# Zotino_HD68_Adapter.net
KiCad netlist of a schematic drawn in Altium Designer
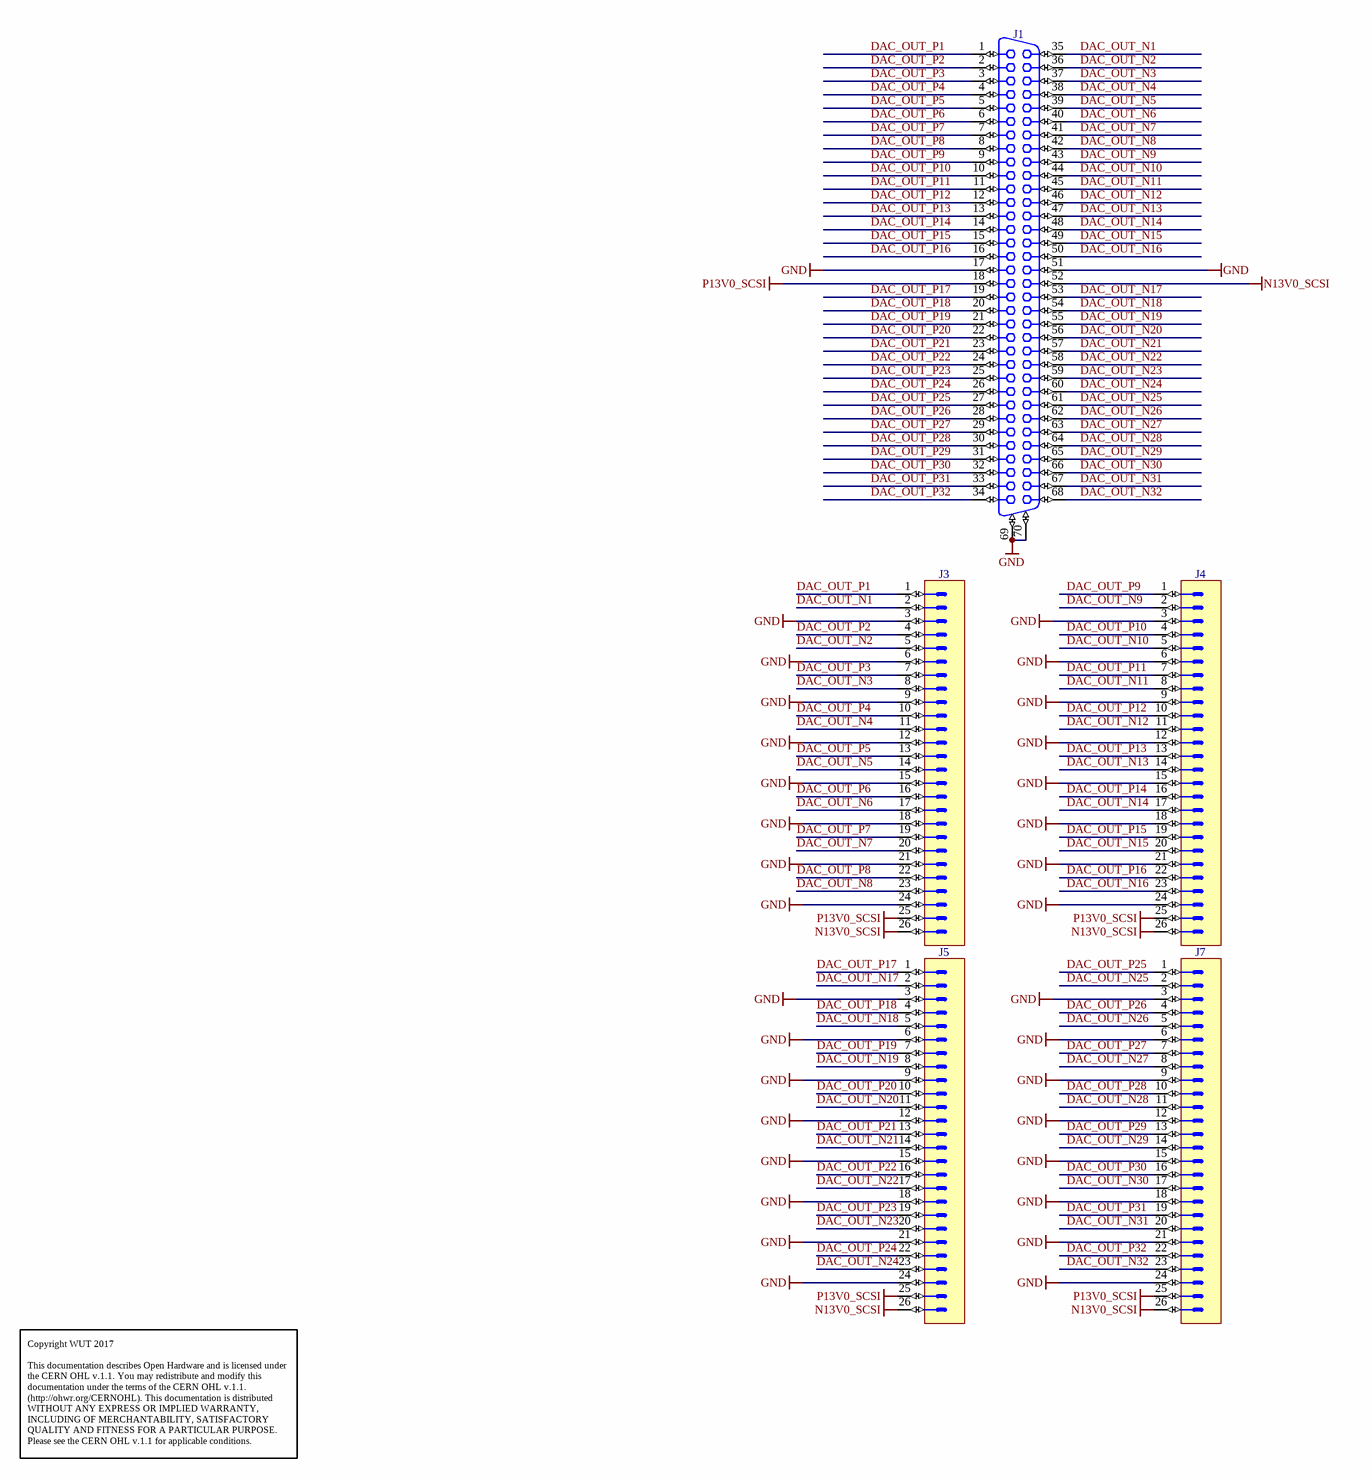
[diagram p0: Zotino_HD68_Adapter.SchDoc]

(export (version "E")
  (design (tool "Eeschema 10.0.6"))
  (components
    (comp (ref "J1")
      (value "D-SUB")
      (footprint "TYCO_5787082-7")
      (description "68 contacts, AMPLIMITE .050\", Right Angled Receptacle Series III")
      (fields
        (field (name "PART NUMBER") "TYCO_5787082-7")
        (field (name "MANUFACTURER") "TYCO ELECTRONICS")
        (field (name "AUTHOR") "CERN DEM JLC")
      )
      (libsource (lib "Connectors") (part "TYCO_5787082-7"))
    )
    (comp (ref "J3")
      (value "Header 26")
      (footprint "3M_N2526-6002RB")
      (description "Connector 26 Male")
      (fields
        (field (name "PART NUMBER") "3M_N2526-6002RB")
        (field (name "MANUFACTURER") "3M")
        (field (name "AUTHOR") "CERN DEM JLC")
      )
      (libsource (lib "Connectors") (part "Connector 26 Male"))
    )
    (comp (ref "J4")
      (value "Header 26")
      (footprint "3M_N2526-6002RB")
      (description "Connector 26 Male")
      (fields
        (field (name "PART NUMBER") "3M_N2526-6002RB")
        (field (name "MANUFACTURER") "3M")
        (field (name "AUTHOR") "CERN DEM JLC")
      )
      (libsource (lib "Connectors") (part "Connector 26 Male"))
    )
    (comp (ref "J5")
      (value "Header 26")
      (footprint "3M_N2526-6002RB")
      (description "Connector 26 Male")
      (fields
        (field (name "PART NUMBER") "3M_N2526-6002RB")
        (field (name "MANUFACTURER") "3M")
        (field (name "AUTHOR") "CERN DEM JLC")
      )
      (libsource (lib "Connectors") (part "Connector 26 Male"))
    )
    (comp (ref "J7")
      (value "Header 26")
      (footprint "3M_N2526-6002RB")
      (description "Connector 26 Male")
      (fields
        (field (name "PART NUMBER") "3M_N2526-6002RB")
        (field (name "MANUFACTURER") "3M")
        (field (name "AUTHOR") "CERN DEM JLC")
      )
      (libsource (lib "Connectors") (part "Connector 26 Male"))
    )
  )
  (nets
    (net (code "1") (name "/DAC_OUT_N1") (class "Default")
      (node (ref "J1") (pin "35") (pinfunction "35_35") (pintype "bidirectional"))
      (node (ref "J3") (pin "2") (pinfunction "2_2") (pintype "bidirectional"))
    )
    (net (code "2") (name "/DAC_OUT_N2") (class "Default")
      (node (ref "J1") (pin "36") (pinfunction "36_36") (pintype "bidirectional"))
      (node (ref "J3") (pin "5") (pinfunction "5_5") (pintype "bidirectional"))
    )
    (net (code "3") (name "/DAC_OUT_N3") (class "Default")
      (node (ref "J1") (pin "37") (pinfunction "37_37") (pintype "bidirectional"))
      (node (ref "J3") (pin "8") (pinfunction "8_8") (pintype "bidirectional"))
    )
    (net (code "4") (name "/DAC_OUT_N4") (class "Default")
      (node (ref "J1") (pin "38") (pinfunction "38_38") (pintype "bidirectional"))
      (node (ref "J3") (pin "11") (pinfunction "11_11") (pintype "bidirectional"))
    )
    (net (code "5") (name "/DAC_OUT_N5") (class "Default")
      (node (ref "J1") (pin "39") (pinfunction "39_39") (pintype "bidirectional"))
      (node (ref "J3") (pin "14") (pinfunction "14_14") (pintype "bidirectional"))
    )
    (net (code "6") (name "/DAC_OUT_N6") (class "Default")
      (node (ref "J1") (pin "40") (pinfunction "40_40") (pintype "bidirectional"))
      (node (ref "J3") (pin "17") (pinfunction "17_17") (pintype "bidirectional"))
    )
    (net (code "7") (name "/DAC_OUT_N7") (class "Default")
      (node (ref "J1") (pin "41") (pinfunction "41_41") (pintype "bidirectional"))
      (node (ref "J3") (pin "20") (pinfunction "20_20") (pintype "bidirectional"))
    )
    (net (code "8") (name "/DAC_OUT_N8") (class "Default")
      (node (ref "J1") (pin "42") (pinfunction "42_42") (pintype "bidirectional"))
      (node (ref "J3") (pin "23") (pinfunction "23_23") (pintype "bidirectional"))
    )
    (net (code "9") (name "/DAC_OUT_N9") (class "Default")
      (node (ref "J1") (pin "43") (pinfunction "43_43") (pintype "bidirectional"))
      (node (ref "J4") (pin "2") (pinfunction "2_2") (pintype "bidirectional"))
    )
    (net (code "10") (name "/DAC_OUT_N10") (class "Default")
      (node (ref "J1") (pin "44") (pinfunction "44_44") (pintype "bidirectional"))
      (node (ref "J4") (pin "5") (pinfunction "5_5") (pintype "bidirectional"))
    )
    (net (code "11") (name "/DAC_OUT_N11") (class "Default")
      (node (ref "J1") (pin "45") (pinfunction "45_45") (pintype "bidirectional"))
      (node (ref "J4") (pin "8") (pinfunction "8_8") (pintype "bidirectional"))
    )
    (net (code "12") (name "/DAC_OUT_N12") (class "Default")
      (node (ref "J1") (pin "46") (pinfunction "46_46") (pintype "bidirectional"))
      (node (ref "J4") (pin "11") (pinfunction "11_11") (pintype "bidirectional"))
    )
    (net (code "13") (name "/DAC_OUT_N13") (class "Default")
      (node (ref "J1") (pin "47") (pinfunction "47_47") (pintype "bidirectional"))
      (node (ref "J4") (pin "14") (pinfunction "14_14") (pintype "bidirectional"))
    )
    (net (code "14") (name "/DAC_OUT_N14") (class "Default")
      (node (ref "J1") (pin "48") (pinfunction "48_48") (pintype "bidirectional"))
      (node (ref "J4") (pin "17") (pinfunction "17_17") (pintype "bidirectional"))
    )
    (net (code "15") (name "/DAC_OUT_N15") (class "Default")
      (node (ref "J1") (pin "49") (pinfunction "49_49") (pintype "bidirectional"))
      (node (ref "J4") (pin "20") (pinfunction "20_20") (pintype "bidirectional"))
    )
    (net (code "16") (name "/DAC_OUT_N16") (class "Default")
      (node (ref "J1") (pin "50") (pinfunction "50_50") (pintype "bidirectional"))
      (node (ref "J4") (pin "23") (pinfunction "23_23") (pintype "bidirectional"))
    )
    (net (code "17") (name "/DAC_OUT_N17") (class "Default")
      (node (ref "J1") (pin "53") (pinfunction "53_53") (pintype "bidirectional"))
      (node (ref "J5") (pin "2") (pinfunction "2_2") (pintype "bidirectional"))
    )
    (net (code "18") (name "/DAC_OUT_N18") (class "Default")
      (node (ref "J1") (pin "54") (pinfunction "54_54") (pintype "bidirectional"))
      (node (ref "J5") (pin "5") (pinfunction "5_5") (pintype "bidirectional"))
    )
    (net (code "19") (name "/DAC_OUT_N19") (class "Default")
      (node (ref "J1") (pin "55") (pinfunction "55_55") (pintype "bidirectional"))
      (node (ref "J5") (pin "8") (pinfunction "8_8") (pintype "bidirectional"))
    )
    (net (code "20") (name "/DAC_OUT_N20") (class "Default")
      (node (ref "J1") (pin "56") (pinfunction "56_56") (pintype "bidirectional"))
      (node (ref "J5") (pin "11") (pinfunction "11_11") (pintype "bidirectional"))
    )
    (net (code "21") (name "/DAC_OUT_N21") (class "Default")
      (node (ref "J1") (pin "57") (pinfunction "57_57") (pintype "bidirectional"))
      (node (ref "J5") (pin "14") (pinfunction "14_14") (pintype "bidirectional"))
    )
    (net (code "22") (name "/DAC_OUT_N22") (class "Default")
      (node (ref "J1") (pin "58") (pinfunction "58_58") (pintype "bidirectional"))
      (node (ref "J5") (pin "17") (pinfunction "17_17") (pintype "bidirectional"))
    )
    (net (code "23") (name "/DAC_OUT_N23") (class "Default")
      (node (ref "J1") (pin "59") (pinfunction "59_59") (pintype "bidirectional"))
      (node (ref "J5") (pin "20") (pinfunction "20_20") (pintype "bidirectional"))
    )
    (net (code "24") (name "/DAC_OUT_N24") (class "Default")
      (node (ref "J1") (pin "60") (pinfunction "60_60") (pintype "bidirectional"))
      (node (ref "J5") (pin "23") (pinfunction "23_23") (pintype "bidirectional"))
    )
    (net (code "25") (name "/DAC_OUT_N25") (class "Default")
      (node (ref "J1") (pin "61") (pinfunction "61_61") (pintype "bidirectional"))
      (node (ref "J7") (pin "2") (pinfunction "2_2") (pintype "bidirectional"))
    )
    (net (code "26") (name "/DAC_OUT_N26") (class "Default")
      (node (ref "J1") (pin "62") (pinfunction "62_62") (pintype "bidirectional"))
      (node (ref "J7") (pin "5") (pinfunction "5_5") (pintype "bidirectional"))
    )
    (net (code "27") (name "/DAC_OUT_N27") (class "Default")
      (node (ref "J1") (pin "63") (pinfunction "63_63") (pintype "bidirectional"))
      (node (ref "J7") (pin "8") (pinfunction "8_8") (pintype "bidirectional"))
    )
    (net (code "28") (name "/DAC_OUT_N28") (class "Default")
      (node (ref "J1") (pin "64") (pinfunction "64_64") (pintype "bidirectional"))
      (node (ref "J7") (pin "11") (pinfunction "11_11") (pintype "bidirectional"))
    )
    (net (code "29") (name "/DAC_OUT_N29") (class "Default")
      (node (ref "J1") (pin "65") (pinfunction "65_65") (pintype "bidirectional"))
      (node (ref "J7") (pin "14") (pinfunction "14_14") (pintype "bidirectional"))
    )
    (net (code "30") (name "/DAC_OUT_N30") (class "Default")
      (node (ref "J1") (pin "66") (pinfunction "66_66") (pintype "bidirectional"))
      (node (ref "J7") (pin "17") (pinfunction "17_17") (pintype "bidirectional"))
    )
    (net (code "31") (name "/DAC_OUT_N31") (class "Default")
      (node (ref "J1") (pin "67") (pinfunction "67_67") (pintype "bidirectional"))
      (node (ref "J7") (pin "20") (pinfunction "20_20") (pintype "bidirectional"))
    )
    (net (code "32") (name "/DAC_OUT_N32") (class "Default")
      (node (ref "J1") (pin "68") (pinfunction "68_68") (pintype "bidirectional"))
      (node (ref "J7") (pin "23") (pinfunction "23_23") (pintype "bidirectional"))
    )
    (net (code "33") (name "/DAC_OUT_P1") (class "Default")
      (node (ref "J1") (pin "1") (pinfunction "1_1") (pintype "bidirectional"))
      (node (ref "J3") (pin "1") (pinfunction "1_1") (pintype "bidirectional"))
    )
    (net (code "34") (name "/DAC_OUT_P2") (class "Default")
      (node (ref "J1") (pin "2") (pinfunction "2_2") (pintype "bidirectional"))
      (node (ref "J3") (pin "4") (pinfunction "4_4") (pintype "bidirectional"))
    )
    (net (code "35") (name "/DAC_OUT_P3") (class "Default")
      (node (ref "J1") (pin "3") (pinfunction "3_3") (pintype "bidirectional"))
      (node (ref "J3") (pin "7") (pinfunction "7_7") (pintype "bidirectional"))
    )
    (net (code "36") (name "/DAC_OUT_P4") (class "Default")
      (node (ref "J1") (pin "4") (pinfunction "4_4") (pintype "bidirectional"))
      (node (ref "J3") (pin "10") (pinfunction "10_10") (pintype "bidirectional"))
    )
    (net (code "37") (name "/DAC_OUT_P5") (class "Default")
      (node (ref "J1") (pin "5") (pinfunction "5_5") (pintype "bidirectional"))
      (node (ref "J3") (pin "13") (pinfunction "13_13") (pintype "bidirectional"))
    )
    (net (code "38") (name "/DAC_OUT_P6") (class "Default")
      (node (ref "J1") (pin "6") (pinfunction "6_6") (pintype "bidirectional"))
      (node (ref "J3") (pin "16") (pinfunction "16_16") (pintype "bidirectional"))
    )
    (net (code "39") (name "/DAC_OUT_P7") (class "Default")
      (node (ref "J1") (pin "7") (pinfunction "7_7") (pintype "bidirectional"))
      (node (ref "J3") (pin "19") (pinfunction "19_19") (pintype "bidirectional"))
    )
    (net (code "40") (name "/DAC_OUT_P8") (class "Default")
      (node (ref "J1") (pin "8") (pinfunction "8_8") (pintype "bidirectional"))
      (node (ref "J3") (pin "22") (pinfunction "22_22") (pintype "bidirectional"))
    )
    (net (code "41") (name "/DAC_OUT_P9") (class "Default")
      (node (ref "J1") (pin "9") (pinfunction "9_9") (pintype "bidirectional"))
      (node (ref "J4") (pin "1") (pinfunction "1_1") (pintype "bidirectional"))
    )
    (net (code "42") (name "/DAC_OUT_P10") (class "Default")
      (node (ref "J1") (pin "10") (pinfunction "10_10") (pintype "bidirectional"))
      (node (ref "J4") (pin "4") (pinfunction "4_4") (pintype "bidirectional"))
    )
    (net (code "43") (name "/DAC_OUT_P11") (class "Default")
      (node (ref "J1") (pin "11") (pinfunction "11_11") (pintype "bidirectional"))
      (node (ref "J4") (pin "7") (pinfunction "7_7") (pintype "bidirectional"))
    )
    (net (code "44") (name "/DAC_OUT_P12") (class "Default")
      (node (ref "J1") (pin "12") (pinfunction "12_12") (pintype "bidirectional"))
      (node (ref "J4") (pin "10") (pinfunction "10_10") (pintype "bidirectional"))
    )
    (net (code "45") (name "/DAC_OUT_P13") (class "Default")
      (node (ref "J1") (pin "13") (pinfunction "13_13") (pintype "bidirectional"))
      (node (ref "J4") (pin "13") (pinfunction "13_13") (pintype "bidirectional"))
    )
    (net (code "46") (name "/DAC_OUT_P14") (class "Default")
      (node (ref "J1") (pin "14") (pinfunction "14_14") (pintype "bidirectional"))
      (node (ref "J4") (pin "16") (pinfunction "16_16") (pintype "bidirectional"))
    )
    (net (code "47") (name "/DAC_OUT_P15") (class "Default")
      (node (ref "J1") (pin "15") (pinfunction "15_15") (pintype "bidirectional"))
      (node (ref "J4") (pin "19") (pinfunction "19_19") (pintype "bidirectional"))
    )
    (net (code "48") (name "/DAC_OUT_P16") (class "Default")
      (node (ref "J1") (pin "16") (pinfunction "16_16") (pintype "bidirectional"))
      (node (ref "J4") (pin "22") (pinfunction "22_22") (pintype "bidirectional"))
    )
    (net (code "49") (name "/DAC_OUT_P17") (class "Default")
      (node (ref "J1") (pin "19") (pinfunction "19_19") (pintype "bidirectional"))
      (node (ref "J5") (pin "1") (pinfunction "1_1") (pintype "bidirectional"))
    )
    (net (code "50") (name "/DAC_OUT_P18") (class "Default")
      (node (ref "J1") (pin "20") (pinfunction "20_20") (pintype "bidirectional"))
      (node (ref "J5") (pin "4") (pinfunction "4_4") (pintype "bidirectional"))
    )
    (net (code "51") (name "/DAC_OUT_P19") (class "Default")
      (node (ref "J1") (pin "21") (pinfunction "21_21") (pintype "bidirectional"))
      (node (ref "J5") (pin "7") (pinfunction "7_7") (pintype "bidirectional"))
    )
    (net (code "52") (name "/DAC_OUT_P20") (class "Default")
      (node (ref "J1") (pin "22") (pinfunction "22_22") (pintype "bidirectional"))
      (node (ref "J5") (pin "10") (pinfunction "10_10") (pintype "bidirectional"))
    )
    (net (code "53") (name "/DAC_OUT_P21") (class "Default")
      (node (ref "J1") (pin "23") (pinfunction "23_23") (pintype "bidirectional"))
      (node (ref "J5") (pin "13") (pinfunction "13_13") (pintype "bidirectional"))
    )
    (net (code "54") (name "/DAC_OUT_P22") (class "Default")
      (node (ref "J1") (pin "24") (pinfunction "24_24") (pintype "bidirectional"))
      (node (ref "J5") (pin "16") (pinfunction "16_16") (pintype "bidirectional"))
    )
    (net (code "55") (name "/DAC_OUT_P23") (class "Default")
      (node (ref "J1") (pin "25") (pinfunction "25_25") (pintype "bidirectional"))
      (node (ref "J5") (pin "19") (pinfunction "19_19") (pintype "bidirectional"))
    )
    (net (code "56") (name "/DAC_OUT_P24") (class "Default")
      (node (ref "J1") (pin "26") (pinfunction "26_26") (pintype "bidirectional"))
      (node (ref "J5") (pin "22") (pinfunction "22_22") (pintype "bidirectional"))
    )
    (net (code "57") (name "/DAC_OUT_P25") (class "Default")
      (node (ref "J1") (pin "27") (pinfunction "27_27") (pintype "bidirectional"))
      (node (ref "J7") (pin "1") (pinfunction "1_1") (pintype "bidirectional"))
    )
    (net (code "58") (name "/DAC_OUT_P26") (class "Default")
      (node (ref "J1") (pin "28") (pinfunction "28_28") (pintype "bidirectional"))
      (node (ref "J7") (pin "4") (pinfunction "4_4") (pintype "bidirectional"))
    )
    (net (code "59") (name "/DAC_OUT_P27") (class "Default")
      (node (ref "J1") (pin "29") (pinfunction "29_29") (pintype "bidirectional"))
      (node (ref "J7") (pin "7") (pinfunction "7_7") (pintype "bidirectional"))
    )
    (net (code "60") (name "/DAC_OUT_P28") (class "Default")
      (node (ref "J1") (pin "30") (pinfunction "30_30") (pintype "bidirectional"))
      (node (ref "J7") (pin "10") (pinfunction "10_10") (pintype "bidirectional"))
    )
    (net (code "61") (name "/DAC_OUT_P29") (class "Default")
      (node (ref "J1") (pin "31") (pinfunction "31_31") (pintype "bidirectional"))
      (node (ref "J7") (pin "13") (pinfunction "13_13") (pintype "bidirectional"))
    )
    (net (code "62") (name "/DAC_OUT_P30") (class "Default")
      (node (ref "J1") (pin "32") (pinfunction "32_32") (pintype "bidirectional"))
      (node (ref "J7") (pin "16") (pinfunction "16_16") (pintype "bidirectional"))
    )
    (net (code "63") (name "/DAC_OUT_P31") (class "Default")
      (node (ref "J1") (pin "33") (pinfunction "33_33") (pintype "bidirectional"))
      (node (ref "J7") (pin "19") (pinfunction "19_19") (pintype "bidirectional"))
    )
    (net (code "64") (name "/DAC_OUT_P32") (class "Default")
      (node (ref "J1") (pin "34") (pinfunction "34_34") (pintype "bidirectional"))
      (node (ref "J7") (pin "22") (pinfunction "22_22") (pintype "bidirectional"))
    )
    (net (code "65") (name "GND") (class "Default")
      (node (ref "J1") (pin "17") (pinfunction "17_17") (pintype "bidirectional"))
      (node (ref "J1") (pin "51") (pinfunction "51_51") (pintype "bidirectional"))
      (node (ref "J1") (pin "69") (pinfunction "69_69") (pintype "bidirectional"))
      (node (ref "J1") (pin "70") (pinfunction "70_70") (pintype "bidirectional"))
      (node (ref "J3") (pin "12") (pinfunction "12_12") (pintype "bidirectional"))
      (node (ref "J3") (pin "15") (pinfunction "15_15") (pintype "bidirectional"))
      (node (ref "J3") (pin "18") (pinfunction "18_18") (pintype "bidirectional"))
      (node (ref "J3") (pin "21") (pinfunction "21_21") (pintype "bidirectional"))
      (node (ref "J3") (pin "24") (pinfunction "24_24") (pintype "bidirectional"))
      (node (ref "J3") (pin "3") (pinfunction "3_3") (pintype "bidirectional"))
      (node (ref "J3") (pin "6") (pinfunction "6_6") (pintype "bidirectional"))
      (node (ref "J3") (pin "9") (pinfunction "9_9") (pintype "bidirectional"))
      (node (ref "J4") (pin "12") (pinfunction "12_12") (pintype "bidirectional"))
      (node (ref "J4") (pin "15") (pinfunction "15_15") (pintype "bidirectional"))
      (node (ref "J4") (pin "18") (pinfunction "18_18") (pintype "bidirectional"))
      (node (ref "J4") (pin "21") (pinfunction "21_21") (pintype "bidirectional"))
      (node (ref "J4") (pin "24") (pinfunction "24_24") (pintype "bidirectional"))
      (node (ref "J4") (pin "3") (pinfunction "3_3") (pintype "bidirectional"))
      (node (ref "J4") (pin "6") (pinfunction "6_6") (pintype "bidirectional"))
      (node (ref "J4") (pin "9") (pinfunction "9_9") (pintype "bidirectional"))
      (node (ref "J5") (pin "12") (pinfunction "12_12") (pintype "bidirectional"))
      (node (ref "J5") (pin "15") (pinfunction "15_15") (pintype "bidirectional"))
      (node (ref "J5") (pin "18") (pinfunction "18_18") (pintype "bidirectional"))
      (node (ref "J5") (pin "21") (pinfunction "21_21") (pintype "bidirectional"))
      (node (ref "J5") (pin "24") (pinfunction "24_24") (pintype "bidirectional"))
      (node (ref "J5") (pin "3") (pinfunction "3_3") (pintype "bidirectional"))
      (node (ref "J5") (pin "6") (pinfunction "6_6") (pintype "bidirectional"))
      (node (ref "J5") (pin "9") (pinfunction "9_9") (pintype "bidirectional"))
      (node (ref "J7") (pin "12") (pinfunction "12_12") (pintype "bidirectional"))
      (node (ref "J7") (pin "15") (pinfunction "15_15") (pintype "bidirectional"))
      (node (ref "J7") (pin "18") (pinfunction "18_18") (pintype "bidirectional"))
      (node (ref "J7") (pin "21") (pinfunction "21_21") (pintype "bidirectional"))
      (node (ref "J7") (pin "24") (pinfunction "24_24") (pintype "bidirectional"))
      (node (ref "J7") (pin "3") (pinfunction "3_3") (pintype "bidirectional"))
      (node (ref "J7") (pin "6") (pinfunction "6_6") (pintype "bidirectional"))
      (node (ref "J7") (pin "9") (pinfunction "9_9") (pintype "bidirectional"))
    )
    (net (code "66") (name "N13V0_SCSI") (class "Default")
      (node (ref "J1") (pin "52") (pinfunction "52_52") (pintype "bidirectional"))
      (node (ref "J3") (pin "26") (pinfunction "26_26") (pintype "bidirectional"))
      (node (ref "J4") (pin "26") (pinfunction "26_26") (pintype "bidirectional"))
      (node (ref "J5") (pin "26") (pinfunction "26_26") (pintype "bidirectional"))
      (node (ref "J7") (pin "26") (pinfunction "26_26") (pintype "bidirectional"))
    )
    (net (code "67") (name "P13V0_SCSI") (class "Default")
      (node (ref "J1") (pin "18") (pinfunction "18_18") (pintype "bidirectional"))
      (node (ref "J3") (pin "25") (pinfunction "25_25") (pintype "bidirectional"))
      (node (ref "J4") (pin "25") (pinfunction "25_25") (pintype "bidirectional"))
      (node (ref "J5") (pin "25") (pinfunction "25_25") (pintype "bidirectional"))
      (node (ref "J7") (pin "25") (pinfunction "25_25") (pintype "bidirectional"))
    )
  )
)
